# YiYiClock.net
KiCad netlist of a schematic drawn in EasyEDA Pro
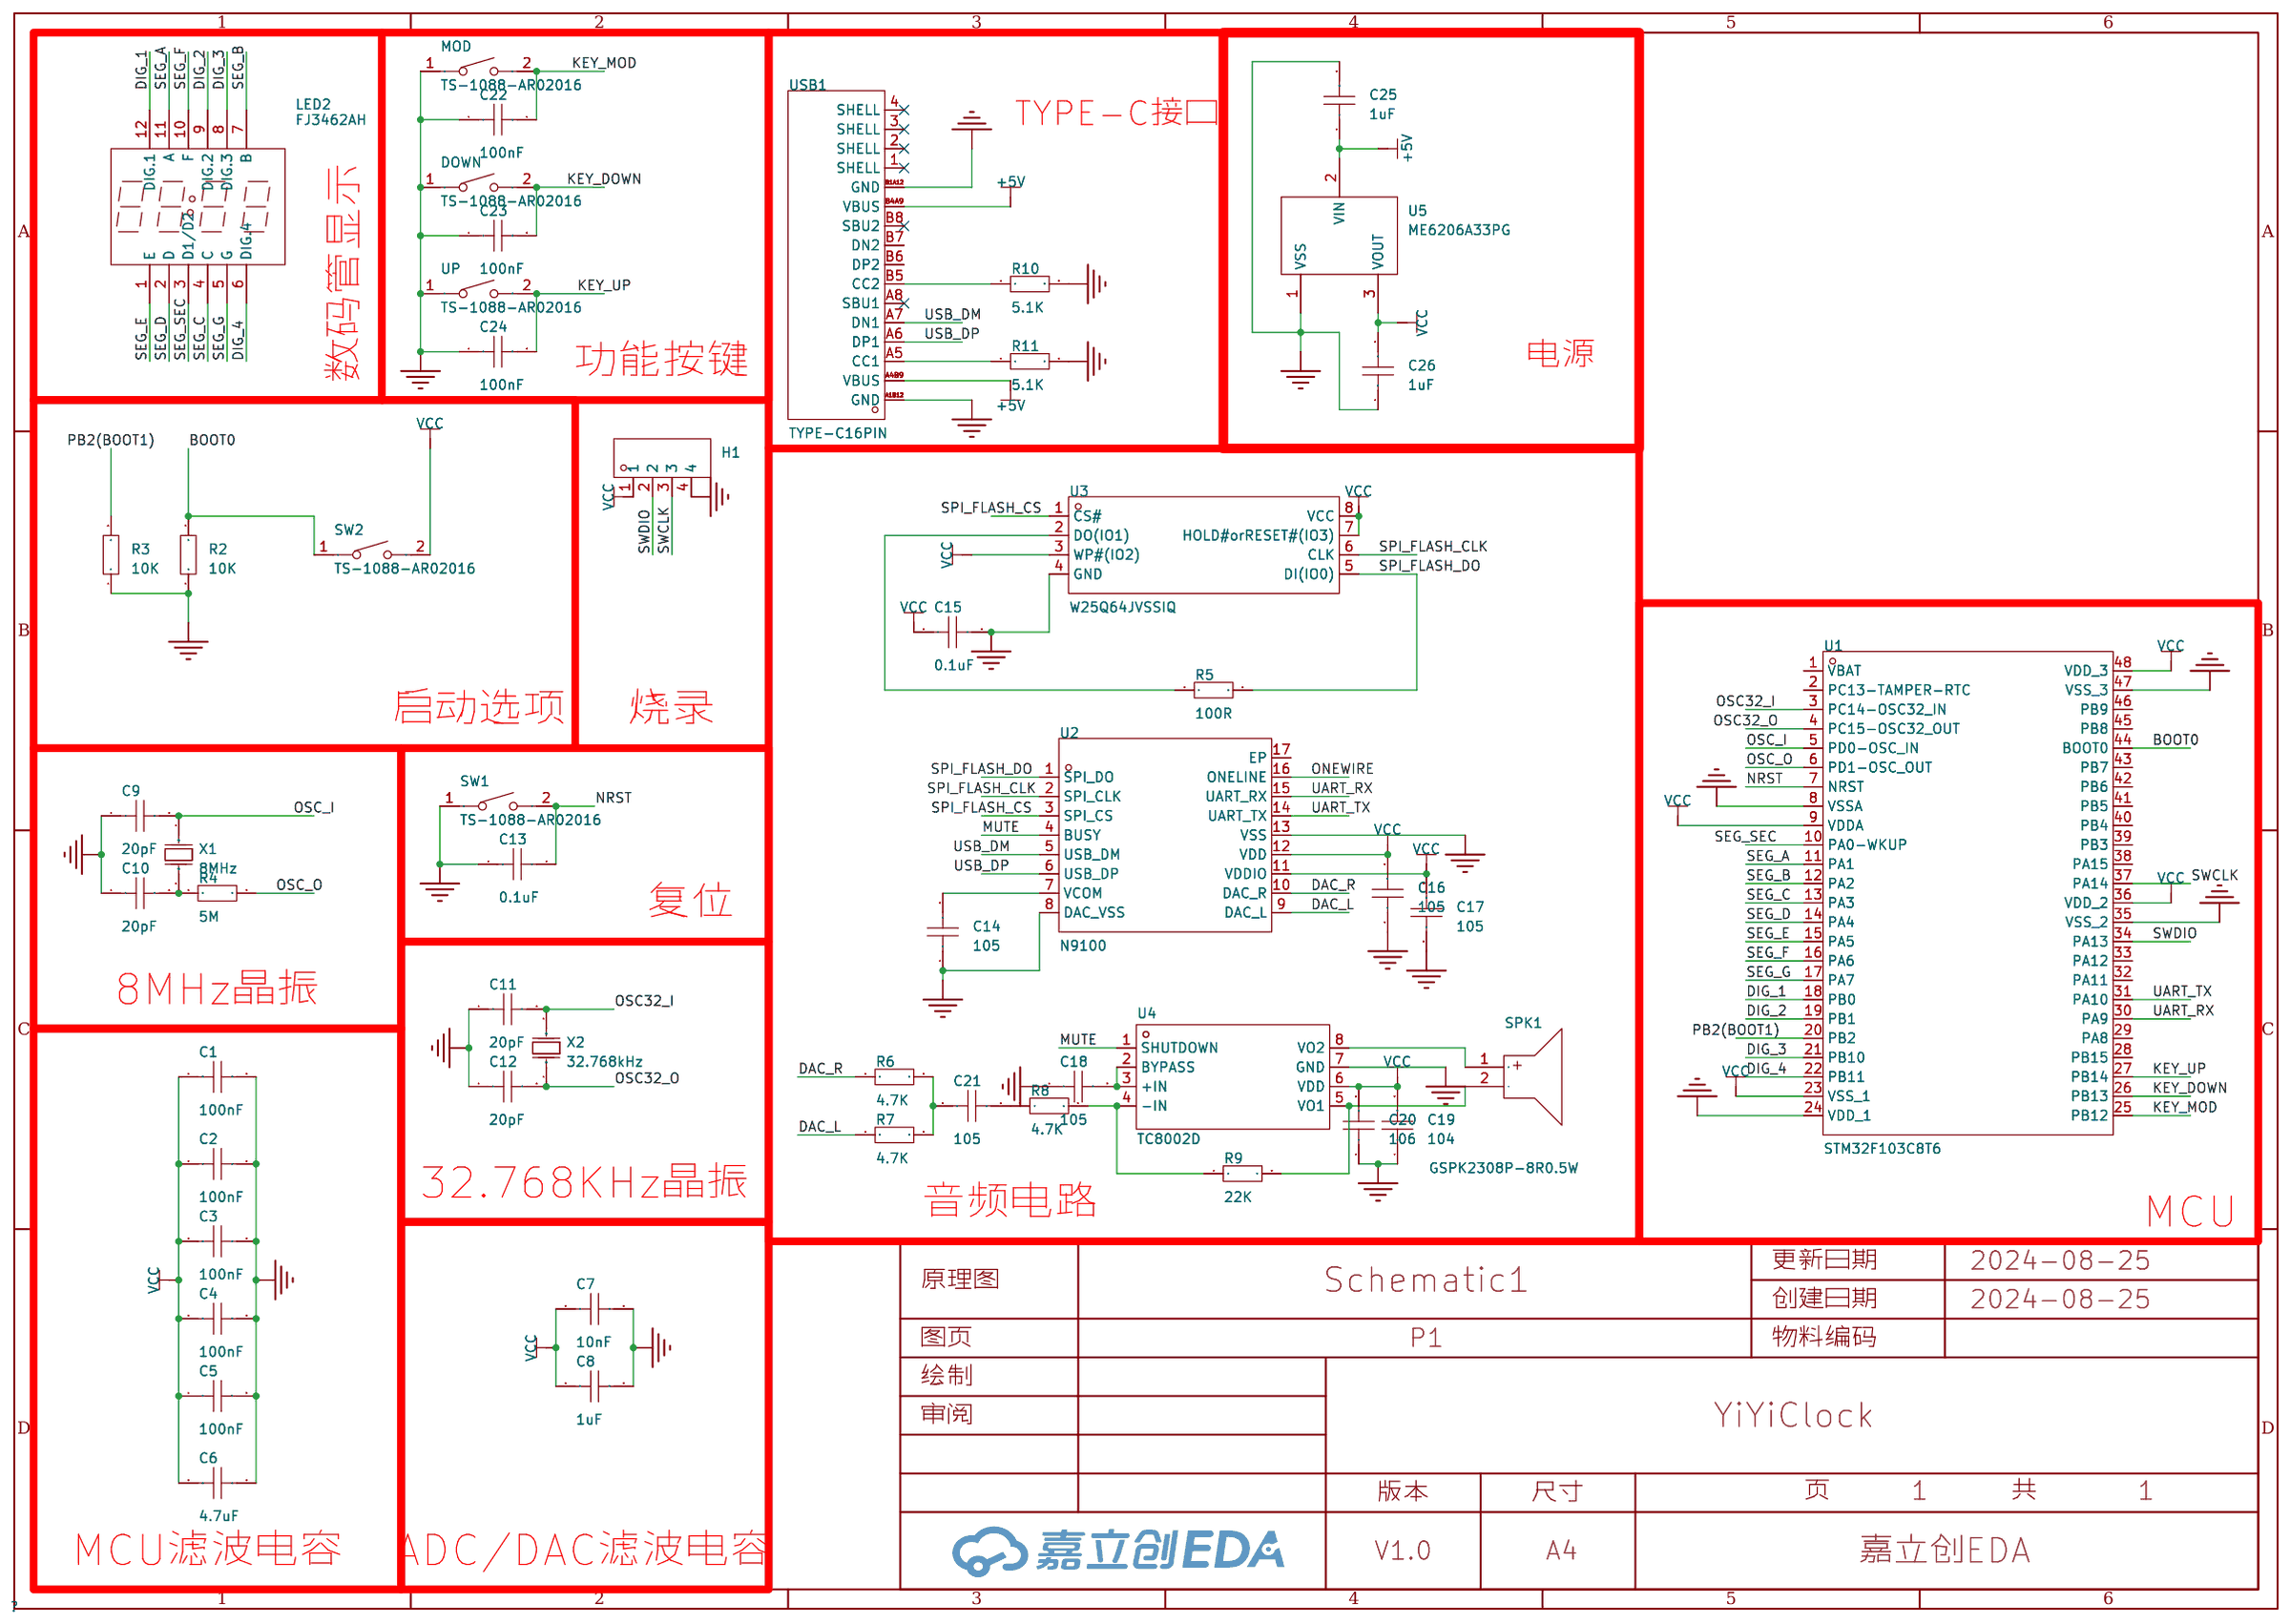
[diagram p0: schematic sheet]

(export (version "E")
  (design (tool "Eeschema 10.0.6"))
  (components
    (comp (ref "C1")
      (value "100nF")
      (footprint "easyedapro:C0805")
      (libsource (lib "easyedapro") (part "CapAcitance"))
    )
    (comp (ref "C2")
      (value "100nF")
      (footprint "easyedapro:C0805")
      (libsource (lib "easyedapro") (part "CapAcitance"))
    )
    (comp (ref "C3")
      (value "100nF")
      (footprint "easyedapro:C0805")
      (libsource (lib "easyedapro") (part "CapAcitance"))
    )
    (comp (ref "C4")
      (value "100nF")
      (footprint "easyedapro:C0805")
      (libsource (lib "easyedapro") (part "CapAcitance"))
    )
    (comp (ref "C5")
      (value "100nF")
      (footprint "easyedapro:C0805")
      (libsource (lib "easyedapro") (part "CapAcitance"))
    )
    (comp (ref "C6")
      (value "4.7uF")
      (footprint "easyedapro:C0805")
      (libsource (lib "easyedapro") (part "CapAcitance"))
    )
    (comp (ref "C7")
      (value "10nF")
      (footprint "easyedapro:C0805")
      (libsource (lib "easyedapro") (part "CapAcitance"))
    )
    (comp (ref "C8")
      (value "1uF")
      (footprint "easyedapro:C0805")
      (libsource (lib "easyedapro") (part "CapAcitance"))
    )
    (comp (ref "C9")
      (value "20pF")
      (footprint "easyedapro:C0805")
      (libsource (lib "easyedapro") (part "CapAcitance"))
    )
    (comp (ref "C10")
      (value "20pF")
      (footprint "easyedapro:C0805")
      (libsource (lib "easyedapro") (part "CapAcitance"))
    )
    (comp (ref "C11")
      (value "20pF")
      (footprint "easyedapro:C0805")
      (libsource (lib "easyedapro") (part "CapAcitance"))
    )
    (comp (ref "C12")
      (value "20pF")
      (footprint "easyedapro:C0805")
      (libsource (lib "easyedapro") (part "CapAcitance"))
    )
    (comp (ref "C13")
      (value "0.1uF")
      (footprint "easyedapro:C0805")
      (libsource (lib "easyedapro") (part "CapAcitance"))
    )
    (comp (ref "C14")
      (value "105")
      (footprint "easyedapro:C0805")
      (libsource (lib "easyedapro") (part "CapAcitance"))
    )
    (comp (ref "C15")
      (value "0.1uF")
      (footprint "easyedapro:C0805")
      (libsource (lib "easyedapro") (part "CapAcitance"))
    )
    (comp (ref "C16")
      (value "105")
      (footprint "easyedapro:C0805")
      (libsource (lib "easyedapro") (part "CapAcitance"))
    )
    (comp (ref "C17")
      (value "105")
      (footprint "easyedapro:C0805")
      (libsource (lib "easyedapro") (part "CapAcitance"))
    )
    (comp (ref "C18")
      (value "105")
      (footprint "easyedapro:C0805")
      (libsource (lib "easyedapro") (part "CapAcitance"))
    )
    (comp (ref "C19")
      (value "104")
      (footprint "easyedapro:C0805")
      (libsource (lib "easyedapro") (part "CapAcitance"))
    )
    (comp (ref "C20")
      (value "106")
      (footprint "easyedapro:C0805")
      (libsource (lib "easyedapro") (part "CapAcitance"))
    )
    (comp (ref "C21")
      (value "105")
      (footprint "easyedapro:C0805")
      (libsource (lib "easyedapro") (part "CapAcitance"))
    )
    (comp (ref "C22")
      (value "100nF")
      (footprint "easyedapro:C0805")
      (libsource (lib "easyedapro") (part "CapAcitance"))
    )
    (comp (ref "C23")
      (value "100nF")
      (footprint "easyedapro:C0805")
      (libsource (lib "easyedapro") (part "CapAcitance"))
    )
    (comp (ref "C24")
      (value "100nF")
      (footprint "easyedapro:C0805")
      (libsource (lib "easyedapro") (part "CapAcitance"))
    )
    (comp (ref "C25")
      (value "1uF")
      (footprint "easyedapro:C0805")
      (libsource (lib "easyedapro") (part "CapAcitance"))
    )
    (comp (ref "C26")
      (value "1uF")
      (footprint "easyedapro:C0805")
      (libsource (lib "easyedapro") (part "CapAcitance"))
    )
    (comp (ref "DOWN")
      (value "TS-1088-AR02016")
      (footprint "easyedapro:SW-SMD_L3.9-W3.0-P4.45")
      (fields (field (name "Manufacturer") "XUNPU(讯普)"))
      (libsource (lib "easyedapro") (part "TS-1088-AR02016"))
    )
    (comp (ref "H1")
      (value "~")
      (footprint "easyedapro:HDR-TH_4P-P2.54-V-M")
      (libsource (lib "easyedapro") (part "PZ254V-11-04P"))
    )
    (comp (ref "LED2")
      (value "FJ3462AH")
      (footprint "easyedapro:LED-SEG-TH_12P-L30.0-W14.0-P2.54-S10.16-BL_FJ3462XH")
      (description "发光颜色:-;")
      (fields (field (name "Manufacturer") "志浩"))
      (libsource (lib "easyedapro") (part "FJ3462AH"))
    )
    (comp (ref "MOD")
      (value "TS-1088-AR02016")
      (footprint "easyedapro:SW-SMD_L3.9-W3.0-P4.45")
      (fields (field (name "Manufacturer") "XUNPU(讯普)"))
      (libsource (lib "easyedapro") (part "TS-1088-AR02016"))
    )
    (comp (ref "R2") (value "10K") (footprint "easyedapro:R0805") (libsource (lib "easyedapro") (part "电阻")))
    (comp (ref "R3") (value "10K") (footprint "easyedapro:R0805") (libsource (lib "easyedapro") (part "电阻")))
    (comp (ref "R4") (value "5M") (footprint "easyedapro:R0805") (libsource (lib "easyedapro") (part "电阻")))
    (comp (ref "R5") (value "100R") (footprint "easyedapro:R0805") (libsource (lib "easyedapro") (part "电阻")))
    (comp (ref "R6") (value "4.7K") (footprint "easyedapro:R0805") (libsource (lib "easyedapro") (part "电阻")))
    (comp (ref "R7") (value "4.7K") (footprint "easyedapro:R0805") (libsource (lib "easyedapro") (part "电阻")))
    (comp (ref "R8") (value "4.7K") (footprint "easyedapro:R0805") (libsource (lib "easyedapro") (part "电阻")))
    (comp (ref "R9") (value "22K") (footprint "easyedapro:R0805") (libsource (lib "easyedapro") (part "电阻")))
    (comp (ref "R10")
      (value "5.1K")
      (footprint "easyedapro:R0805")
      (libsource (lib "easyedapro") (part "电阻"))
    )
    (comp (ref "R11")
      (value "5.1K")
      (footprint "easyedapro:R0805")
      (libsource (lib "easyedapro") (part "电阻"))
    )
    (comp (ref "SPK1")
      (value "GSPK2308P-8R0.5W")
      (footprint "easyedapro:SPK-TH_BD23.0-P10.00-D0.8-L-RD")
      (fields (field (name "Manufacturer") "INGHAi(赢海)"))
      (libsource (lib "easyedapro") (part "GSPK2308P-8R0.5W"))
    )
    (comp (ref "SW1")
      (value "TS-1088-AR02016")
      (footprint "easyedapro:SW-SMD_L3.9-W3.0-P4.45")
      (fields (field (name "Manufacturer") "XUNPU(讯普)"))
      (libsource (lib "easyedapro") (part "TS-1088-AR02016"))
    )
    (comp (ref "SW2")
      (value "TS-1088-AR02016")
      (footprint "easyedapro:SW-SMD_L3.9-W3.0-P4.45")
      (fields (field (name "Manufacturer") "XUNPU(讯普)"))
      (libsource (lib "easyedapro") (part "TS-1088-AR02016"))
    )
    (comp (ref "U1")
      (value "STM32F103C8T6")
      (footprint "easyedapro:LQFP-48_L7.0-W7.0-P0.50-LS9.0-BL")
      (description "CPU内核:ARM-M3;程序存储容量:64KB;RAM总容量:20KB;GPIO端口数量:37;工作电压范围:2V~3.6V;CPU最大主频:72MHz;程序存储器类型:FLASH;")
      (fields (field (name "Manufacturer") "ST(意法半导体)"))
      (libsource (lib "easyedapro") (part "STM32F103C8T6"))
    )
    (comp (ref "U2")
      (value "N9100")
      (footprint "easyedapro:ESOP-16_L9.9-W3.9-P1.27-LS6.0-BL-EP-1")
      (description "类型:处理器;接口:串行;采样频率:4kHz~48kHz;")
      (fields (field (name "Manufacturer") "NINE CIHP(九芯电子)"))
      (libsource (lib "easyedapro") (part "N9100"))
    )
    (comp (ref "U3")
      (value "W25Q64JVSSIQ")
      (footprint "easyedapro:SOIC-8_L5.3-W5.3-P1.27-LS8.0-BL")
      (fields (field (name "Manufacturer") "WINBOND(华邦)"))
      (libsource (lib "easyedapro") (part "W25Q64JVSSIQ_C179171"))
    )
    (comp (ref "U4")
      (value "TC8002D")
      (footprint "easyedapro:SOIC-8_L5.0-W4.0-P1.27-LS6.0-BL")
      (description "功放类型:-;扬声器通道数:单声道;输出功率:3Wx1@3Ω;")
      (fields (field (name "Manufacturer") "FM(富满)"))
      (libsource (lib "easyedapro") (part "TC8002D"))
    )
    (comp (ref "U5")
      (value "ME6206A33PG")
      (footprint "easyedapro:SOT-89-3_L4.5-W2.5-P1.50-LS4.2-BR")
      (description "输出类型:固定;最大输入电压:6V;输出电压:3.3V;最大输出电流:300mA;电源纹波抑制比(PSRR):50dB@(1kHz);输出极性:正极;")
      (fields (field (name "Manufacturer") "MICRONE(南京微盟)"))
      (libsource (lib "easyedapro") (part "ME6206A33PG"))
    )
    (comp (ref "UP")
      (value "TS-1088-AR02016")
      (footprint "easyedapro:SW-SMD_L3.9-W3.0-P4.45")
      (fields (field (name "Manufacturer") "XUNPU(讯普)"))
      (libsource (lib "easyedapro") (part "TS-1088-AR02016"))
    )
    (comp (ref "USB1")
      (value "TYPE-C16PIN")
      (footprint "easyedapro:USB-C-SMD_TYPE-C16PIN")
      (description "连接器类型:Type-C;标准:-;公母:母;端口数量:1;触点数量:16P;安装方式:卧贴;额定电流 - 电源:3A;工作温度范围:-40°C~+85°C;")
      (fields (field (name "Manufacturer") "SHOU HAN(首韩)"))
      (libsource (lib "easyedapro") (part "TYPE-C16PIN"))
    )
    (comp (ref "X1")
      (value "8MHz")
      (footprint "easyedapro:CRYSTAL-SMD_L11.5-W4.8-LS12.7")
      (description "晶振类型:贴片晶振;频率:8MHz;常温频差:±20ppm;外接负载电容:20pF;频率稳定度(全温):±30ppm;")
      (fields (field (name "Manufacturer Part") "X49SM8MSD2SC") (field (name "Manufacturer") "YXC(扬兴晶振)"))
      (libsource (lib "easyedapro") (part "X49SM8MSD2SC"))
    )
    (comp (ref "X2")
      (value "32.768kHz")
      (footprint "easyedapro:OSC-SMD_L3.2-W1.5")
      (description "晶振类型:贴片晶振;频率:32.768kHz;常温频差:±20ppm;外接负载电容:12.5pF;")
      (fields
        (field (name "Manufacturer Part") "TCXM32768K2NGDCZT2T")
        (field (name "Manufacturer") "YJX(雅晶鑫)")
      )
      (libsource (lib "easyedapro") (part "TMXLi-310S 32.768KHZ 12.5PF 20PPM"))
    )
  )
  (nets
    (net (code "1") (name "+5V") (class "Default")
      (node (ref "C25") (pin "1") (pinfunction "1_1") (pintype "input"))
      (node (ref "U5") (pin "2") (pinfunction "VIN_2") (pintype "input"))
      (node (ref "USB1") (pin "A4B9") (pinfunction "VBUS_A4B9") (pintype "unspecified"))
      (node (ref "USB1") (pin "B4A9") (pinfunction "VBUS_B4A9") (pintype "unspecified"))
    )
    (net (code "2") (name "/BOOT0") (class "Default")
      (node (ref "R2") (pin "2") (pinfunction "2_2") (pintype "input"))
      (node (ref "SW2") (pin "1") (pinfunction "1_1") (pintype "unspecified"))
      (node (ref "U1") (pin "44") (pinfunction "BOOT0_44") (pintype "unspecified"))
    )
    (net (code "3") (name "/DAC_L") (class "Default")
      (node (ref "R7") (pin "1") (pinfunction "1_1") (pintype "input"))
      (node (ref "U2") (pin "9") (pinfunction "DAC_L_9") (pintype "unspecified"))
    )
    (net (code "4") (name "/DAC_R") (class "Default")
      (node (ref "R6") (pin "1") (pinfunction "1_1") (pintype "input"))
      (node (ref "U2") (pin "10") (pinfunction "DAC_R_10") (pintype "unspecified"))
    )
    (net (code "5") (name "/DIG_1") (class "Default")
      (node (ref "LED2") (pin "12") (pinfunction "DIG.1_12") (pintype "unspecified"))
      (node (ref "U1") (pin "18") (pinfunction "PB0_18") (pintype "unspecified"))
    )
    (net (code "6") (name "/DIG_2") (class "Default")
      (node (ref "LED2") (pin "9") (pinfunction "DIG.2_9") (pintype "unspecified"))
      (node (ref "U1") (pin "19") (pinfunction "PB1_19") (pintype "unspecified"))
    )
    (net (code "7") (name "/DIG_3") (class "Default")
      (node (ref "LED2") (pin "8") (pinfunction "DIG.3_8") (pintype "unspecified"))
      (node (ref "U1") (pin "21") (pinfunction "PB10_21") (pintype "unspecified"))
    )
    (net (code "8") (name "/DIG_4") (class "Default")
      (node (ref "LED2") (pin "6") (pinfunction "DIG.4_6") (pintype "unspecified"))
      (node (ref "U1") (pin "22") (pinfunction "PB11_22") (pintype "unspecified"))
    )
    (net (code "9") (name "/KEY_DOWN") (class "Default")
      (node (ref "C23") (pin "2") (pinfunction "2_2") (pintype "input"))
      (node (ref "DOWN") (pin "2") (pinfunction "2_2") (pintype "unspecified"))
      (node (ref "U1") (pin "26") (pinfunction "PB13_26") (pintype "unspecified"))
    )
    (net (code "10") (name "/KEY_MOD") (class "Default")
      (node (ref "C22") (pin "2") (pinfunction "2_2") (pintype "input"))
      (node (ref "MOD") (pin "2") (pinfunction "2_2") (pintype "unspecified"))
      (node (ref "U1") (pin "25") (pinfunction "PB12_25") (pintype "unspecified"))
    )
    (net (code "11") (name "/KEY_UP") (class "Default")
      (node (ref "C24") (pin "2") (pinfunction "2_2") (pintype "input"))
      (node (ref "U1") (pin "27") (pinfunction "PB14_27") (pintype "unspecified"))
      (node (ref "UP") (pin "2") (pinfunction "2_2") (pintype "unspecified"))
    )
    (net (code "12") (name "/MUTE") (class "Default")
      (node (ref "U2") (pin "4") (pinfunction "BUSY_4") (pintype "unspecified"))
      (node (ref "U4") (pin "1") (pinfunction "SHUTDOWN_1") (pintype "unspecified"))
    )
    (net (code "13") (name "/NRST") (class "Default")
      (node (ref "C13") (pin "2") (pinfunction "2_2") (pintype "input"))
      (node (ref "SW1") (pin "2") (pinfunction "2_2") (pintype "unspecified"))
      (node (ref "U1") (pin "7") (pinfunction "NRST_7") (pintype "unspecified"))
    )
    (net (code "14") (name "/ONEWIRE") (class "Default")
      (node (ref "U2") (pin "16") (pinfunction "ONELINE_16") (pintype "unspecified"))
    )
    (net (code "15") (name "/OSC32_I") (class "Default")
      (node (ref "C11") (pin "2") (pinfunction "2_2") (pintype "input"))
      (node (ref "U1") (pin "3") (pinfunction "PC14-OSC32_IN_3") (pintype "unspecified"))
      (node (ref "X2") (pin "2") (pinfunction "OSC2_2") (pintype "input"))
    )
    (net (code "16") (name "/OSC32_O") (class "Default")
      (node (ref "C12") (pin "2") (pinfunction "2_2") (pintype "input"))
      (node (ref "U1") (pin "4") (pinfunction "PC15-OSC32_OUT_4") (pintype "unspecified"))
      (node (ref "X2") (pin "1") (pinfunction "OSC1_1") (pintype "input"))
    )
    (net (code "17") (name "/OSC_I") (class "Default")
      (node (ref "C9") (pin "2") (pinfunction "2_2") (pintype "input"))
      (node (ref "U1") (pin "5") (pinfunction "PD0-OSC_IN_5") (pintype "unspecified"))
      (node (ref "X1") (pin "1") (pinfunction "OSC1_1") (pintype "input"))
    )
    (net (code "18") (name "/OSC_O") (class "Default")
      (node (ref "R4") (pin "2") (pinfunction "2_2") (pintype "input"))
      (node (ref "U1") (pin "6") (pinfunction "PD1-OSC_OUT_6") (pintype "unspecified"))
    )
    (net (code "19") (name "/PB2(BOOT1)") (class "Default")
      (node (ref "R3") (pin "2") (pinfunction "2_2") (pintype "input"))
      (node (ref "U1") (pin "20") (pinfunction "PB2_20") (pintype "unspecified"))
    )
    (net (code "20") (name "/SEG_A") (class "Default")
      (node (ref "LED2") (pin "11") (pinfunction "A_11") (pintype "unspecified"))
      (node (ref "U1") (pin "11") (pinfunction "PA1_11") (pintype "unspecified"))
    )
    (net (code "21") (name "/SEG_B") (class "Default")
      (node (ref "LED2") (pin "7") (pinfunction "B_7") (pintype "unspecified"))
      (node (ref "U1") (pin "12") (pinfunction "PA2_12") (pintype "unspecified"))
    )
    (net (code "22") (name "/SEG_C") (class "Default")
      (node (ref "LED2") (pin "4") (pinfunction "C_4") (pintype "unspecified"))
      (node (ref "U1") (pin "13") (pinfunction "PA3_13") (pintype "unspecified"))
    )
    (net (code "23") (name "/SEG_D") (class "Default")
      (node (ref "LED2") (pin "2") (pinfunction "D_2") (pintype "unspecified"))
      (node (ref "U1") (pin "14") (pinfunction "PA4_14") (pintype "unspecified"))
    )
    (net (code "24") (name "/SEG_E") (class "Default")
      (node (ref "LED2") (pin "1") (pinfunction "E_1") (pintype "unspecified"))
      (node (ref "U1") (pin "15") (pinfunction "PA5_15") (pintype "unspecified"))
    )
    (net (code "25") (name "/SEG_F") (class "Default")
      (node (ref "LED2") (pin "10") (pinfunction "F_10") (pintype "unspecified"))
      (node (ref "U1") (pin "16") (pinfunction "PA6_16") (pintype "unspecified"))
    )
    (net (code "26") (name "/SEG_G") (class "Default")
      (node (ref "LED2") (pin "5") (pinfunction "G_5") (pintype "unspecified"))
      (node (ref "U1") (pin "17") (pinfunction "PA7_17") (pintype "unspecified"))
    )
    (net (code "27") (name "/SEG_SEC") (class "Default")
      (node (ref "LED2") (pin "3") (pinfunction "D1/D2_3") (pintype "unspecified"))
      (node (ref "U1") (pin "10") (pinfunction "PA0-WKUP_10") (pintype "unspecified"))
    )
    (net (code "28") (name "/SPI_FLASH_CLK") (class "Default")
      (node (ref "U2") (pin "2") (pinfunction "SPI_CLK_2") (pintype "unspecified"))
      (node (ref "U3") (pin "6") (pinfunction "CLK_6") (pintype "unspecified"))
    )
    (net (code "29") (name "/SPI_FLASH_CS") (class "Default")
      (node (ref "U2") (pin "3") (pinfunction "SPI_CS_3") (pintype "unspecified"))
      (node (ref "U3") (pin "1") (pinfunction "CS#_1") (pintype "unspecified"))
    )
    (net (code "30") (name "/SPI_FLASH_DO") (class "Default")
      (node (ref "R5") (pin "2") (pinfunction "2_2") (pintype "input"))
      (node (ref "U2") (pin "1") (pinfunction "SPI_DO_1") (pintype "unspecified"))
      (node (ref "U3") (pin "5") (pinfunction "DI(IO0)_5") (pintype "unspecified"))
    )
    (net (code "31") (name "/SWCLK") (class "Default")
      (node (ref "H1") (pin "3") (pinfunction "3_3") (pintype "unspecified"))
      (node (ref "U1") (pin "37") (pinfunction "PA14_37") (pintype "unspecified"))
    )
    (net (code "32") (name "/SWDIO") (class "Default")
      (node (ref "H1") (pin "2") (pinfunction "2_2") (pintype "unspecified"))
      (node (ref "U1") (pin "34") (pinfunction "PA13_34") (pintype "unspecified"))
    )
    (net (code "33") (name "/UART_RX") (class "Default")
      (node (ref "U1") (pin "30") (pinfunction "PA9_30") (pintype "unspecified"))
      (node (ref "U2") (pin "15") (pinfunction "UART_RX_15") (pintype "unspecified"))
    )
    (net (code "34") (name "/UART_TX") (class "Default")
      (node (ref "U1") (pin "31") (pinfunction "PA10_31") (pintype "unspecified"))
      (node (ref "U2") (pin "14") (pinfunction "UART_TX_14") (pintype "unspecified"))
    )
    (net (code "35") (name "/USB_DM") (class "Default")
      (node (ref "U2") (pin "5") (pinfunction "USB_DM_5") (pintype "unspecified"))
      (node (ref "USB1") (pin "A7") (pinfunction "DN1_A7") (pintype "unspecified"))
    )
    (net (code "36") (name "/USB_DP") (class "Default")
      (node (ref "U2") (pin "6") (pinfunction "USB_DP_6") (pintype "unspecified"))
      (node (ref "USB1") (pin "A6") (pinfunction "DP1_A6") (pintype "unspecified"))
    )
    (net (code "37") (name "GND") (class "Default")
      (node (ref "C1") (pin "2") (pinfunction "2_2") (pintype "input"))
      (node (ref "C10") (pin "1") (pinfunction "1_1") (pintype "input"))
      (node (ref "C11") (pin "1") (pinfunction "1_1") (pintype "input"))
      (node (ref "C12") (pin "1") (pinfunction "1_1") (pintype "input"))
      (node (ref "C13") (pin "1") (pinfunction "1_1") (pintype "input"))
      (node (ref "C14") (pin "1") (pinfunction "1_1") (pintype "input"))
      (node (ref "C15") (pin "2") (pinfunction "2_2") (pintype "input"))
      (node (ref "C16") (pin "1") (pinfunction "1_1") (pintype "input"))
      (node (ref "C17") (pin "1") (pinfunction "1_1") (pintype "input"))
      (node (ref "C18") (pin "1") (pinfunction "1_1") (pintype "input"))
      (node (ref "C19") (pin "1") (pinfunction "1_1") (pintype "input"))
      (node (ref "C2") (pin "2") (pinfunction "2_2") (pintype "input"))
      (node (ref "C20") (pin "1") (pinfunction "1_1") (pintype "input"))
      (node (ref "C22") (pin "1") (pinfunction "1_1") (pintype "input"))
      (node (ref "C23") (pin "1") (pinfunction "1_1") (pintype "input"))
      (node (ref "C24") (pin "1") (pinfunction "1_1") (pintype "input"))
      (node (ref "C25") (pin "2") (pinfunction "2_2") (pintype "input"))
      (node (ref "C26") (pin "1") (pinfunction "1_1") (pintype "input"))
      (node (ref "C3") (pin "2") (pinfunction "2_2") (pintype "input"))
      (node (ref "C4") (pin "2") (pinfunction "2_2") (pintype "input"))
      (node (ref "C5") (pin "2") (pinfunction "2_2") (pintype "input"))
      (node (ref "C6") (pin "2") (pinfunction "2_2") (pintype "input"))
      (node (ref "C7") (pin "2") (pinfunction "2_2") (pintype "input"))
      (node (ref "C8") (pin "2") (pinfunction "2_2") (pintype "input"))
      (node (ref "C9") (pin "1") (pinfunction "1_1") (pintype "input"))
      (node (ref "DOWN") (pin "1") (pinfunction "1_1") (pintype "unspecified"))
      (node (ref "H1") (pin "4") (pinfunction "4_4") (pintype "unspecified"))
      (node (ref "MOD") (pin "1") (pinfunction "1_1") (pintype "unspecified"))
      (node (ref "R10") (pin "2") (pinfunction "2_2") (pintype "input"))
      (node (ref "R11") (pin "2") (pinfunction "2_2") (pintype "input"))
      (node (ref "R2") (pin "1") (pinfunction "1_1") (pintype "input"))
      (node (ref "R3") (pin "1") (pinfunction "1_1") (pintype "input"))
      (node (ref "SW1") (pin "1") (pinfunction "1_1") (pintype "unspecified"))
      (node (ref "U1") (pin "24") (pinfunction "VDD_1_24") (pintype "unspecified"))
      (node (ref "U1") (pin "35") (pinfunction "VSS_2_35") (pintype "unspecified"))
      (node (ref "U1") (pin "47") (pinfunction "VSS_3_47") (pintype "unspecified"))
      (node (ref "U1") (pin "8") (pinfunction "VSSA_8") (pintype "unspecified"))
      (node (ref "U2") (pin "13") (pinfunction "VSS_13") (pintype "unspecified"))
      (node (ref "U2") (pin "8") (pinfunction "DAC_VSS_8") (pintype "unspecified"))
      (node (ref "U3") (pin "4") (pinfunction "GND_4") (pintype "unspecified"))
      (node (ref "U4") (pin "7") (pinfunction "GND_7") (pintype "unspecified"))
      (node (ref "U5") (pin "1") (pinfunction "VSS_1") (pintype "input"))
      (node (ref "UP") (pin "1") (pinfunction "1_1") (pintype "unspecified"))
      (node (ref "USB1") (pin "A1B12") (pinfunction "GND_A1B12") (pintype "unspecified"))
      (node (ref "USB1") (pin "B1A12") (pinfunction "GND_B1A12") (pintype "unspecified"))
    )
    (net (code "38") (name "Net-(C21-Pad1)") (class "Default")
      (node (ref "C21") (pin "1") (pinfunction "1_1") (pintype "input"))
      (node (ref "R6") (pin "2") (pinfunction "2_2") (pintype "input"))
      (node (ref "R7") (pin "2") (pinfunction "2_2") (pintype "input"))
    )
    (net (code "39") (name "Net-(C21-Pad2)") (class "Default")
      (node (ref "C21") (pin "2") (pinfunction "2_2") (pintype "input"))
      (node (ref "R8") (pin "1") (pinfunction "1_1") (pintype "input"))
    )
    (net (code "40") (name "Net-(SPK1-+)") (class "Default")
      (node (ref "SPK1") (pin "1") (pinfunction "+_1") (pintype "unspecified"))
      (node (ref "U4") (pin "8") (pinfunction "VO2_8") (pintype "unspecified"))
    )
    (net (code "41") (name "Net-(SPK1--)") (class "Default")
      (node (ref "R9") (pin "2") (pinfunction "2_2") (pintype "input"))
      (node (ref "SPK1") (pin "2") (pinfunction "-_2") (pintype "unspecified"))
      (node (ref "U4") (pin "5") (pinfunction "VO1_5") (pintype "unspecified"))
    )
    (net (code "42") (name "Net-(U2-VCOM)") (class "Default")
      (node (ref "C14") (pin "2") (pinfunction "2_2") (pintype "input"))
      (node (ref "U2") (pin "7") (pinfunction "VCOM_7") (pintype "unspecified"))
    )
    (net (code "43") (name "Net-(U3-DO(IO1))") (class "Default")
      (node (ref "R5") (pin "1") (pinfunction "1_1") (pintype "input"))
      (node (ref "U3") (pin "2") (pinfunction "DO(IO1)_2") (pintype "unspecified"))
    )
    (net (code "44") (name "Net-(U4-+IN)") (class "Default")
      (node (ref "C18") (pin "2") (pinfunction "2_2") (pintype "input"))
      (node (ref "U4") (pin "2") (pinfunction "BYPASS_2") (pintype "unspecified"))
      (node (ref "U4") (pin "3") (pinfunction "+IN_3") (pintype "unspecified"))
    )
    (net (code "45") (name "Net-(U4--IN)") (class "Default")
      (node (ref "R8") (pin "2") (pinfunction "2_2") (pintype "input"))
      (node (ref "R9") (pin "1") (pinfunction "1_1") (pintype "input"))
      (node (ref "U4") (pin "4") (pinfunction "-IN_4") (pintype "unspecified"))
    )
    (net (code "46") (name "Net-(USB1-CC1)") (class "Default")
      (node (ref "R11") (pin "1") (pinfunction "1_1") (pintype "input"))
      (node (ref "USB1") (pin "A5") (pinfunction "CC1_A5") (pintype "unspecified"))
    )
    (net (code "47") (name "Net-(USB1-CC2)") (class "Default")
      (node (ref "R10") (pin "1") (pinfunction "1_1") (pintype "input"))
      (node (ref "USB1") (pin "B5") (pinfunction "CC2_B5") (pintype "unspecified"))
    )
    (net (code "48") (name "Net-(X1-OSC2)") (class "Default")
      (node (ref "C10") (pin "2") (pinfunction "2_2") (pintype "input"))
      (node (ref "R4") (pin "1") (pinfunction "1_1") (pintype "input"))
      (node (ref "X1") (pin "2") (pinfunction "OSC2_2") (pintype "input"))
    )
    (net (code "49") (name "VCC") (class "Default")
      (node (ref "C1") (pin "1") (pinfunction "1_1") (pintype "input"))
      (node (ref "C15") (pin "1") (pinfunction "1_1") (pintype "input"))
      (node (ref "C16") (pin "2") (pinfunction "2_2") (pintype "input"))
      (node (ref "C17") (pin "2") (pinfunction "2_2") (pintype "input"))
      (node (ref "C19") (pin "2") (pinfunction "2_2") (pintype "input"))
      (node (ref "C2") (pin "1") (pinfunction "1_1") (pintype "input"))
      (node (ref "C20") (pin "2") (pinfunction "2_2") (pintype "input"))
      (node (ref "C26") (pin "2") (pinfunction "2_2") (pintype "input"))
      (node (ref "C3") (pin "1") (pinfunction "1_1") (pintype "input"))
      (node (ref "C4") (pin "1") (pinfunction "1_1") (pintype "input"))
      (node (ref "C5") (pin "1") (pinfunction "1_1") (pintype "input"))
      (node (ref "C6") (pin "1") (pinfunction "1_1") (pintype "input"))
      (node (ref "C7") (pin "1") (pinfunction "1_1") (pintype "input"))
      (node (ref "C8") (pin "1") (pinfunction "1_1") (pintype "input"))
      (node (ref "H1") (pin "1") (pinfunction "1_1") (pintype "unspecified"))
      (node (ref "SW2") (pin "2") (pinfunction "2_2") (pintype "unspecified"))
      (node (ref "U1") (pin "23") (pinfunction "VSS_1_23") (pintype "unspecified"))
      (node (ref "U1") (pin "36") (pinfunction "VDD_2_36") (pintype "unspecified"))
      (node (ref "U1") (pin "48") (pinfunction "VDD_3_48") (pintype "unspecified"))
      (node (ref "U1") (pin "9") (pinfunction "VDDA_9") (pintype "unspecified"))
      (node (ref "U2") (pin "11") (pinfunction "VDDIO_11") (pintype "unspecified"))
      (node (ref "U2") (pin "12") (pinfunction "VDD_12") (pintype "unspecified"))
      (node (ref "U3") (pin "3") (pinfunction "WP#(IO2)_3") (pintype "unspecified"))
      (node (ref "U3") (pin "7") (pinfunction "HOLD#orRESET#(IO3)_7") (pintype "unspecified"))
      (node (ref "U3") (pin "8") (pinfunction "VCC_8") (pintype "unspecified"))
      (node (ref "U4") (pin "6") (pinfunction "VDD_6") (pintype "unspecified"))
      (node (ref "U5") (pin "3") (pinfunction "VOUT_3") (pintype "input"))
    )
    (net (code "50") (name "unconnected-(U1-PA8-Pad29)") (class "Default")
      (node (ref "U1") (pin "29") (pinfunction "PA8_29") (pintype "unspecified"))
    )
    (net (code "51") (name "unconnected-(U1-PA11-Pad32)") (class "Default")
      (node (ref "U1") (pin "32") (pinfunction "PA11_32") (pintype "unspecified"))
    )
    (net (code "52") (name "unconnected-(U1-PA12-Pad33)") (class "Default")
      (node (ref "U1") (pin "33") (pinfunction "PA12_33") (pintype "unspecified"))
    )
    (net (code "53") (name "unconnected-(U1-PA15-Pad38)") (class "Default")
      (node (ref "U1") (pin "38") (pinfunction "PA15_38") (pintype "unspecified"))
    )
    (net (code "54") (name "unconnected-(U1-PB3-Pad39)") (class "Default")
      (node (ref "U1") (pin "39") (pinfunction "PB3_39") (pintype "unspecified"))
    )
    (net (code "55") (name "unconnected-(U1-PB4-Pad40)") (class "Default")
      (node (ref "U1") (pin "40") (pinfunction "PB4_40") (pintype "unspecified"))
    )
    (net (code "56") (name "unconnected-(U1-PB5-Pad41)") (class "Default")
      (node (ref "U1") (pin "41") (pinfunction "PB5_41") (pintype "unspecified"))
    )
    (net (code "57") (name "unconnected-(U1-PB6-Pad42)") (class "Default")
      (node (ref "U1") (pin "42") (pinfunction "PB6_42") (pintype "unspecified"))
    )
    (net (code "58") (name "unconnected-(U1-PB7-Pad43)") (class "Default")
      (node (ref "U1") (pin "43") (pinfunction "PB7_43") (pintype "unspecified"))
    )
    (net (code "59") (name "unconnected-(U1-PB8-Pad45)") (class "Default")
      (node (ref "U1") (pin "45") (pinfunction "PB8_45") (pintype "unspecified"))
    )
    (net (code "60") (name "unconnected-(U1-PB9-Pad46)") (class "Default")
      (node (ref "U1") (pin "46") (pinfunction "PB9_46") (pintype "unspecified"))
    )
    (net (code "61") (name "unconnected-(U1-PB15-Pad28)") (class "Default")
      (node (ref "U1") (pin "28") (pinfunction "PB15_28") (pintype "unspecified"))
    )
    (net (code "62") (name "unconnected-(U1-PC13-TAMPER-RTC-Pad2)") (class "Default")
      (node (ref "U1") (pin "2") (pinfunction "PC13-TAMPER-RTC_2") (pintype "unspecified"))
    )
    (net (code "63") (name "unconnected-(U1-VBAT-Pad1)") (class "Default")
      (node (ref "U1") (pin "1") (pinfunction "VBAT_1") (pintype "unspecified"))
    )
    (net (code "64") (name "unconnected-(U2-EP-Pad17)") (class "Default")
      (node (ref "U2") (pin "17") (pinfunction "EP_17") (pintype "unspecified"))
    )
    (net (code "65") (name "unconnected-(USB1-DN2-PadB7)") (class "Default")
      (node (ref "USB1") (pin "B7") (pinfunction "DN2_B7") (pintype "unspecified"))
    )
    (net (code "66") (name "unconnected-(USB1-DP2-PadB6)") (class "Default")
      (node (ref "USB1") (pin "B6") (pinfunction "DP2_B6") (pintype "unspecified"))
    )
    (net (code "67") (name "unconnected-(USB1-SBU1-PadA8)") (class "Default")
      (node (ref "USB1") (pin "A8") (pinfunction "SBU1_A8") (pintype "unspecified+no_connect"))
    )
    (net (code "68") (name "unconnected-(USB1-SBU2-PadB8)") (class "Default")
      (node (ref "USB1") (pin "B8") (pinfunction "SBU2_B8") (pintype "unspecified+no_connect"))
    )
    (net (code "69") (name "unconnected-(USB1-SHELL-Pad1)") (class "Default")
      (node (ref "USB1") (pin "1") (pinfunction "SHELL_1") (pintype "unspecified+no_connect"))
    )
    (net (code "70") (name "unconnected-(USB1-SHELL-Pad2)") (class "Default")
      (node (ref "USB1") (pin "2") (pinfunction "SHELL_2") (pintype "unspecified+no_connect"))
    )
    (net (code "71") (name "unconnected-(USB1-SHELL-Pad3)") (class "Default")
      (node (ref "USB1") (pin "3") (pinfunction "SHELL_3") (pintype "unspecified+no_connect"))
    )
    (net (code "72") (name "unconnected-(USB1-SHELL-Pad4)") (class "Default")
      (node (ref "USB1") (pin "4") (pinfunction "SHELL_4") (pintype "unspecified+no_connect"))
    )
  )
)
